# uart_level_shifter.net
KiCad netlist of a schematic drawn in EAGLE
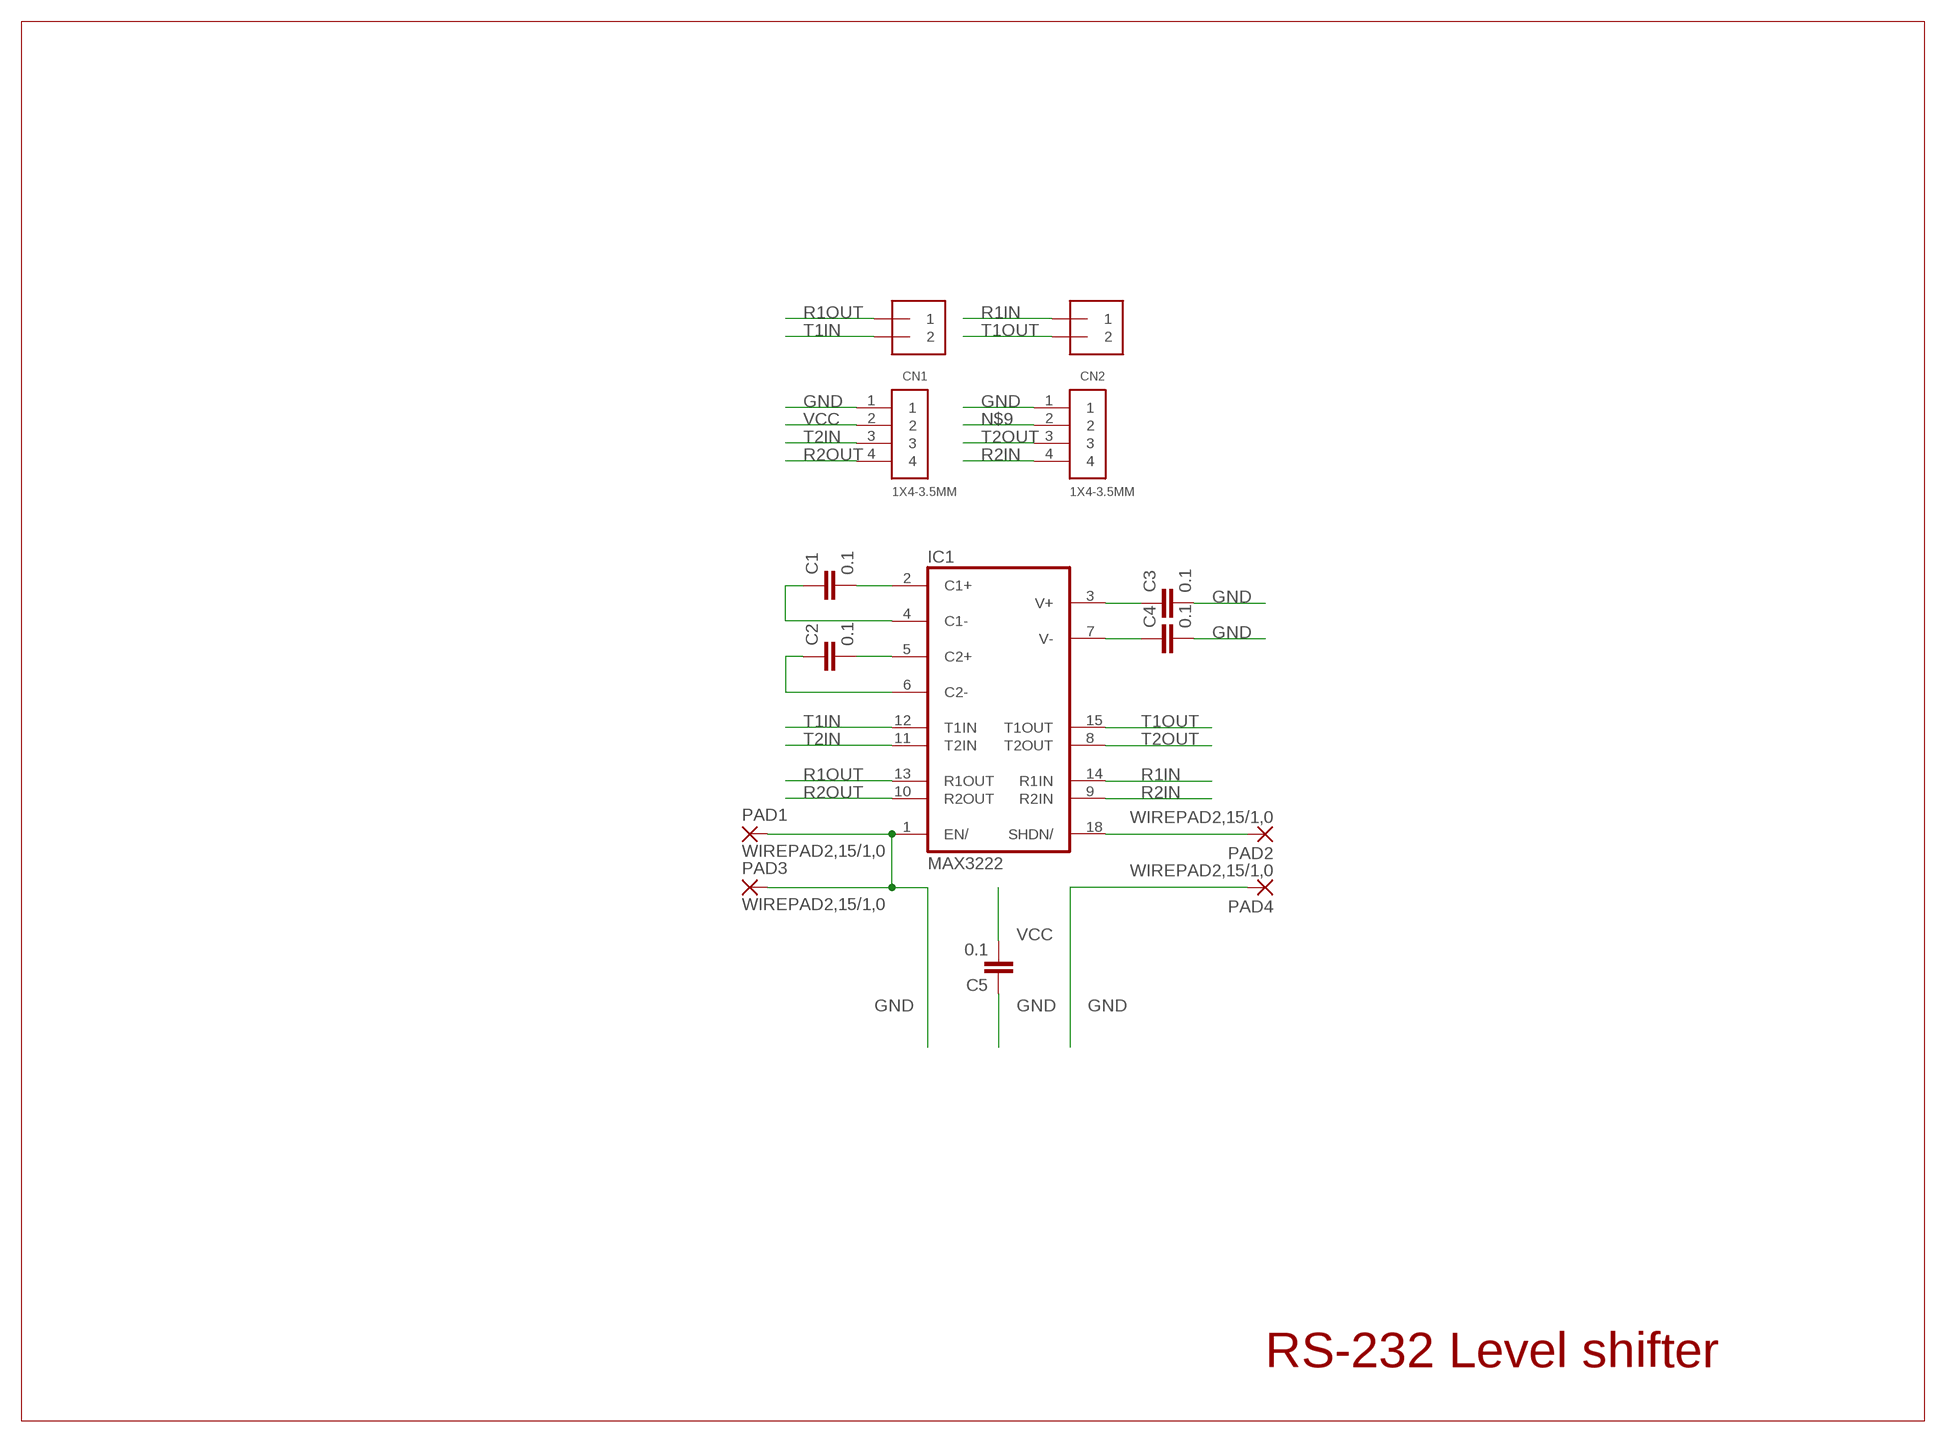
[diagram p0: schematic, sheet 1]

(export (version "E")
  (design (tool "Eeschema 10.0.6"))
  (components
    (comp (ref "C1")
      (value "0.1")
      (footprint "eagle-import:C0805")
      (libsource (lib "eagle-import") (part "C-EUC0805"))
    )
    (comp (ref "C2")
      (value "0.1")
      (footprint "eagle-import:C0805")
      (libsource (lib "eagle-import") (part "C-EUC0805"))
    )
    (comp (ref "C3")
      (value "0.1")
      (footprint "eagle-import:C0805")
      (libsource (lib "eagle-import") (part "C-EUC0805"))
    )
    (comp (ref "C4")
      (value "0.1")
      (footprint "eagle-import:C0805")
      (libsource (lib "eagle-import") (part "C-EUC0805"))
    )
    (comp (ref "C5")
      (value "0.1")
      (footprint "eagle-import:C0805")
      (libsource (lib "eagle-import") (part "C-EUC0805"))
    )
    (comp (ref "CN1")
      (value "1X4-3.5MM")
      (footprint "eagle-import:1X04-3.5MM")
      (libsource (lib "eagle-import") (part "1X4-3.5MM"))
    )
    (comp (ref "CN2")
      (value "1X4-3.5MM")
      (footprint "eagle-import:1X04-3.5MM")
      (libsource (lib "eagle-import") (part "1X4-3.5MM"))
    )
    (comp (ref "IC1")
      (value "MAX3222")
      (footprint "eagle-import:DIL18")
      (fields (field (name "MPN") "MAX3222EPN+"))
      (libsource (lib "eagle-import") (part "MAX3222"))
    )
    (comp (ref "J1")
      (value "1X2-3.5MM")
      (footprint "eagle-import:1X2-3.5MM")
      (libsource (lib "eagle-import") (part "1X2-3.5MM"))
    )
    (comp (ref "J2")
      (value "1X2-3.5MM")
      (footprint "eagle-import:1X2-3.5MM")
      (libsource (lib "eagle-import") (part "1X2-3.5MM"))
    )
    (comp (ref "PAD1")
      (value "WIREPAD2,15/1,0")
      (footprint "eagle-import:2,15_1,0")
      (libsource (lib "eagle-import") (part "WIREPAD2,15/1,0"))
    )
    (comp (ref "PAD2")
      (value "WIREPAD2,15/1,0")
      (footprint "eagle-import:2,15_1,0")
      (libsource (lib "eagle-import") (part "WIREPAD2,15/1,0"))
    )
    (comp (ref "PAD3")
      (value "WIREPAD2,15/1,0")
      (footprint "eagle-import:2,15_1,0")
      (libsource (lib "eagle-import") (part "WIREPAD2,15/1,0"))
    )
    (comp (ref "PAD4")
      (value "WIREPAD2,15/1,0")
      (footprint "eagle-import:2,15_1,0")
      (libsource (lib "eagle-import") (part "WIREPAD2,15/1,0"))
    )
  )
  (nets
    (net (code "1") (name "/GND") (class "Default")
      (node (ref "C3") (pin "2") (pinfunction "2_2") (pintype "passive"))
      (node (ref "C4") (pin "2") (pinfunction "2_2") (pintype "passive"))
      (node (ref "C5") (pin "1") (pinfunction "1_1") (pintype "passive"))
      (node (ref "CN1") (pin "1") (pinfunction "1_1") (pintype "bidirectional"))
      (node (ref "CN2") (pin "1") (pinfunction "1_1") (pintype "bidirectional"))
      (node (ref "IC1") (pin "1") (pinfunction "EN/_1") (pintype "input"))
      (node (ref "PAD1") (pin "1") (pinfunction "P_1") (pintype "passive"))
      (node (ref "PAD3") (pin "1") (pinfunction "P_1") (pintype "passive"))
      (node (ref "PAD4") (pin "1") (pinfunction "P_1") (pintype "passive"))
    )
    (net (code "2") (name "/N$9") (class "Default")
      (node (ref "CN2") (pin "2") (pinfunction "2_2") (pintype "bidirectional"))
    )
    (net (code "3") (name "/R1IN") (class "Default")
      (node (ref "IC1") (pin "14") (pinfunction "R1IN_14") (pintype "input"))
      (node (ref "J2") (pin "1") (pinfunction "1_1") (pintype "passive"))
    )
    (net (code "4") (name "/R1OUT") (class "Default")
      (node (ref "IC1") (pin "13") (pinfunction "R1OUT_13") (pintype "output"))
      (node (ref "J1") (pin "1") (pinfunction "1_1") (pintype "passive"))
    )
    (net (code "5") (name "/R2IN") (class "Default")
      (node (ref "CN2") (pin "4") (pinfunction "4_4") (pintype "bidirectional"))
      (node (ref "IC1") (pin "9") (pinfunction "R2IN_9") (pintype "input"))
    )
    (net (code "6") (name "/R2OUT") (class "Default")
      (node (ref "CN1") (pin "4") (pinfunction "4_4") (pintype "bidirectional"))
      (node (ref "IC1") (pin "10") (pinfunction "R2OUT_10") (pintype "output"))
    )
    (net (code "7") (name "/T1IN") (class "Default")
      (node (ref "IC1") (pin "12") (pinfunction "T1IN_12") (pintype "input"))
      (node (ref "J1") (pin "2") (pinfunction "2_2") (pintype "passive"))
    )
    (net (code "8") (name "/T1OUT") (class "Default")
      (node (ref "IC1") (pin "15") (pinfunction "T1OUT_15") (pintype "output"))
      (node (ref "J2") (pin "2") (pinfunction "2_2") (pintype "passive"))
    )
    (net (code "9") (name "/T2IN") (class "Default")
      (node (ref "CN1") (pin "3") (pinfunction "3_3") (pintype "bidirectional"))
      (node (ref "IC1") (pin "11") (pinfunction "T2IN_11") (pintype "input"))
    )
    (net (code "10") (name "/T2OUT") (class "Default")
      (node (ref "CN2") (pin "3") (pinfunction "3_3") (pintype "bidirectional"))
      (node (ref "IC1") (pin "8") (pinfunction "T2OUT_8") (pintype "output"))
    )
    (net (code "11") (name "/VCC") (class "Default")
      (node (ref "C5") (pin "2") (pinfunction "2_2") (pintype "passive"))
      (node (ref "CN1") (pin "2") (pinfunction "2_2") (pintype "bidirectional"))
    )
    (net (code "12") (name "Net-(IC1A-C1+)") (class "Default")
      (node (ref "C1") (pin "2") (pinfunction "2_2") (pintype "passive"))
      (node (ref "IC1") (pin "2") (pinfunction "C1+_2") (pintype "passive"))
    )
    (net (code "13") (name "Net-(IC1A-C1-)") (class "Default")
      (node (ref "C1") (pin "1") (pinfunction "1_1") (pintype "passive"))
      (node (ref "IC1") (pin "4") (pinfunction "C1-_4") (pintype "passive"))
    )
    (net (code "14") (name "Net-(IC1A-C2+)") (class "Default")
      (node (ref "C2") (pin "2") (pinfunction "2_2") (pintype "passive"))
      (node (ref "IC1") (pin "5") (pinfunction "C2+_5") (pintype "passive"))
    )
    (net (code "15") (name "Net-(IC1A-C2-)") (class "Default")
      (node (ref "C2") (pin "1") (pinfunction "1_1") (pintype "passive"))
      (node (ref "IC1") (pin "6") (pinfunction "C2-_6") (pintype "passive"))
    )
    (net (code "16") (name "Net-(IC1A-SHDN{slash})") (class "Default")
      (node (ref "IC1") (pin "18") (pinfunction "SHDN/_18") (pintype "input"))
      (node (ref "PAD2") (pin "1") (pinfunction "P_1") (pintype "passive"))
    )
    (net (code "17") (name "Net-(IC1A-V+)") (class "Default")
      (node (ref "C3") (pin "1") (pinfunction "1_1") (pintype "passive"))
      (node (ref "IC1") (pin "3") (pinfunction "V+_3") (pintype "passive"))
    )
    (net (code "18") (name "Net-(IC1A-V-)") (class "Default")
      (node (ref "C4") (pin "1") (pinfunction "1_1") (pintype "passive"))
      (node (ref "IC1") (pin "7") (pinfunction "V-_7") (pintype "passive"))
    )
  )
)
